# Main_Board.net
KiCad netlist of a schematic drawn in Altium Designer
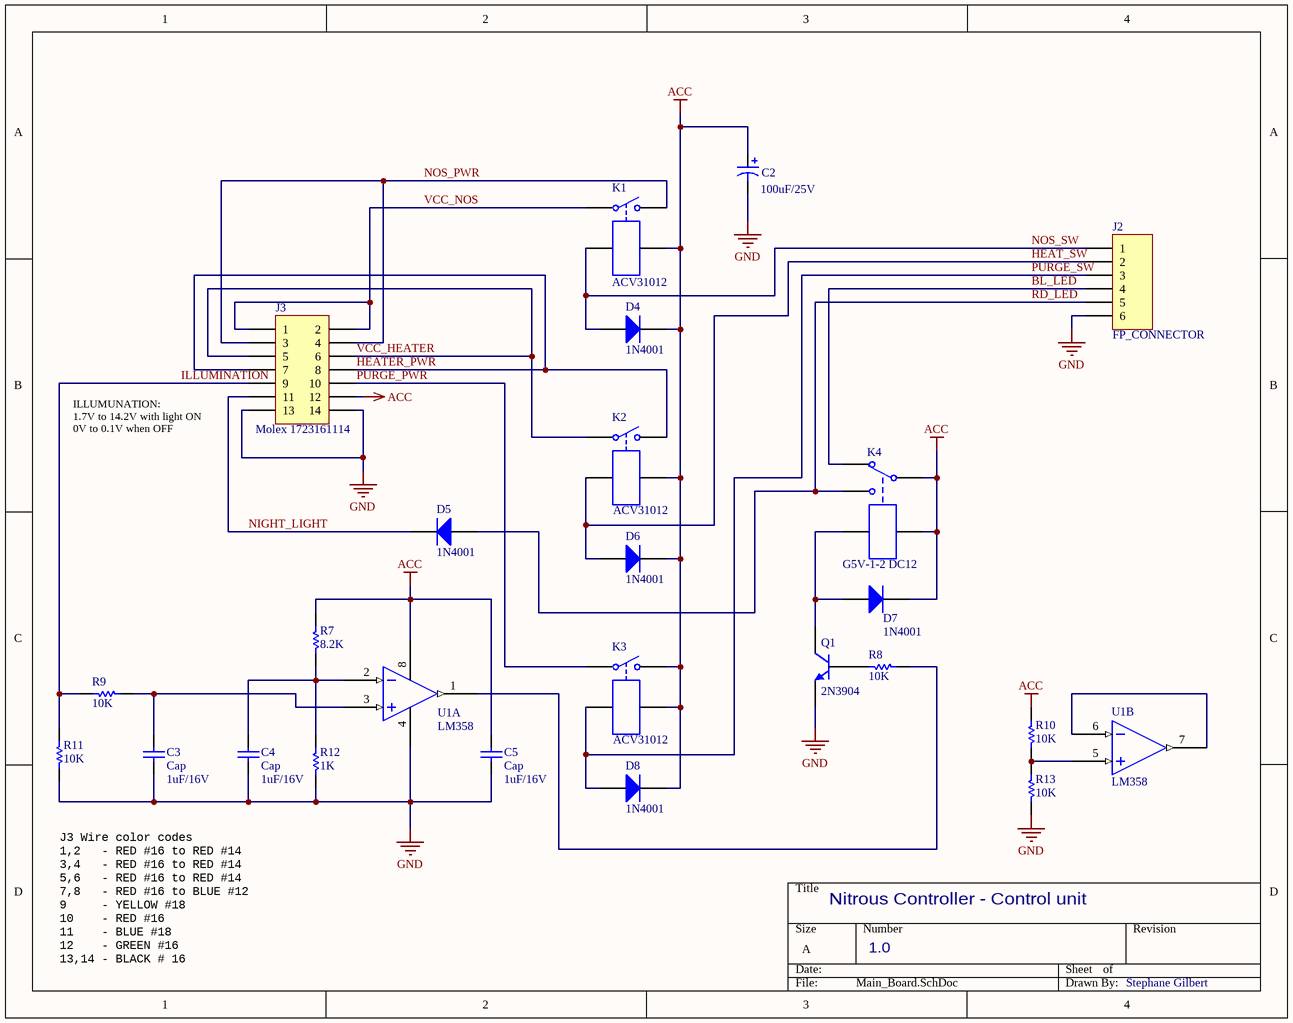
[diagram p0: Main_Board.SchDoc]

(export (version "E")
  (design (tool "Eeschema 10.0.6"))
  (components
    (comp (ref "C2")
      (value "100uF/25V")
      (footprint "RB_3.5MM")
      (description "UBW1E101MPD1TD")
      (fields (field (name "Comment") "Cap Pol1") (field (name "PUBLISHER") "Altium Limited"))
      (libsource (lib "Miscellaneous Devices") (part "Cap Pol1"))
    )
    (comp (ref "C3")
      (value "Cap")
      (footprint "RAD-0.2")
      (description "FA26X8R1E105KNU06")
      (fields (field (name "ALTIUM_VALUE") "1uF/16V") (field (name "PUBLISHER") "Altium Limited"))
      (libsource (lib "Miscellaneous Devices") (part "Cap"))
    )
    (comp (ref "C4")
      (value "Cap")
      (footprint "RAD-0.2")
      (description "FA26X8R1E105KNU06")
      (fields (field (name "ALTIUM_VALUE") "1uF/16V") (field (name "PUBLISHER") "Altium Limited"))
      (libsource (lib "Miscellaneous Devices") (part "Cap"))
    )
    (comp (ref "C5")
      (value "Cap")
      (footprint "RAD-0.2")
      (description "FA26X8R1E105KNU06")
      (fields (field (name "ALTIUM_VALUE") "1uF/16V") (field (name "PUBLISHER") "Altium Limited"))
      (libsource (lib "Miscellaneous Devices") (part "Cap"))
    )
    (comp (ref "D4")
      (value "1N4001")
      (footprint "DO-41")
      (description "1 Amp General Purpose Rectifier")
      (fields (field (name "PUBLISHER") "Altium Limited"))
      (libsource (lib "Miscellaneous Devices") (part "Diode 1N4001"))
    )
    (comp (ref "D5")
      (value "1N4001")
      (footprint "DO-41")
      (description "1 Amp General Purpose Rectifier")
      (fields (field (name "PUBLISHER") "Altium Limited"))
      (libsource (lib "Miscellaneous Devices") (part "Diode 1N4001"))
    )
    (comp (ref "D6")
      (value "1N4001")
      (footprint "DO-41")
      (description "1 Amp General Purpose Rectifier")
      (fields (field (name "PUBLISHER") "Altium Limited"))
      (libsource (lib "Miscellaneous Devices") (part "Diode 1N4001"))
    )
    (comp (ref "D7")
      (value "1N4001")
      (footprint "DO-41")
      (description "1 Amp General Purpose Rectifier")
      (fields (field (name "PUBLISHER") "Altium Limited"))
      (libsource (lib "Miscellaneous Devices") (part "Diode 1N4001"))
    )
    (comp (ref "D8")
      (value "1N4001")
      (footprint "DO-41")
      (description "1 Amp General Purpose Rectifier")
      (fields (field (name "PUBLISHER") "Altium Limited"))
      (libsource (lib "Miscellaneous Devices") (part "Diode 1N4001"))
    )
    (comp (ref "J2")
      (value "FP_CONNECTOR")
      (footprint "MOLEX_5329_6POS_RA")
      (description "Header, 6-Pin")
      (fields (field (name "PUBLISHER") "Altium Limited"))
      (libsource (lib "Miscellaneous Connectors") (part "Header 6"))
    )
    (comp (ref "J3")
      (value "Molex 1723161114")
      (footprint "MOLEX_ULTRA_FIT_14_POS_RA")
      (description "Header, 7-Pin, Dual row")
      (fields (field (name "PUBLISHER") "Altium Limited"))
      (libsource (lib "Miscellaneous Connectors") (part "Header 7X2"))
    )
    (comp (ref "K1")
      (value "ACV31012")
      (footprint "RL_MICRO_ISO_ACV")
      (description "Single-Pole Single-Throw Relay")
      (fields (field (name "PUBLISHER") "Altium Limited"))
      (libsource (lib "Miscellaneous Devices") (part "Relay-SPST"))
    )
    (comp (ref "K2")
      (value "ACV31012")
      (footprint "RL_MICRO_ISO_ACV")
      (description "Single-Pole Single-Throw Relay")
      (fields (field (name "PUBLISHER") "Altium Limited"))
      (libsource (lib "Miscellaneous Devices") (part "Relay-SPST"))
    )
    (comp (ref "K3")
      (value "ACV31012")
      (footprint "RL_MICRO_ISO_ACV")
      (description "Single-Pole Single-Throw Relay")
      (fields (field (name "PUBLISHER") "Altium Limited"))
      (libsource (lib "Miscellaneous Devices") (part "Relay-SPST"))
    )
    (comp (ref "K4")
      (value "G5V-1-2 DC12")
      (footprint "RL_G5V-1")
      (description "Single-Pole Dual-Throw Relay")
      (fields (field (name "PUBLISHER") "Altium Limited"))
      (libsource (lib "Miscellaneous Devices") (part "Relay-SPDT"))
    )
    (comp (ref "Q1")
      (value "2N3904")
      (footprint "TO-92")
      (description "NPN Bipolar Transistor")
      (fields (field (name "PUBLISHER") "Altium Limited"))
      (libsource (lib "Miscellaneous Devices") (part "NPN"))
    )
    (comp (ref "R7")
      (value "8.2K")
      (footprint "AXIAL-0.4")
      (description "Resistor")
      (fields (field (name "Comment") "Res1") (field (name "PUBLISHER") "Altium Limited"))
      (libsource (lib "Miscellaneous Devices") (part "Res1"))
    )
    (comp (ref "R8")
      (value "10K")
      (footprint "AXIAL-0.4")
      (description "Resistor")
      (fields (field (name "Comment") "Res1") (field (name "PUBLISHER") "Altium Limited"))
      (libsource (lib "Miscellaneous Devices") (part "Res1"))
    )
    (comp (ref "R9")
      (value "10K")
      (footprint "AXIAL-0.4")
      (description "Resistor")
      (fields (field (name "Comment") "Res1") (field (name "PUBLISHER") "Altium Limited"))
      (libsource (lib "Miscellaneous Devices") (part "Res1"))
    )
    (comp (ref "R10")
      (value "10K")
      (footprint "AXIAL-0.4")
      (description "Resistor")
      (fields (field (name "Comment") "Res1") (field (name "PUBLISHER") "Altium Limited"))
      (libsource (lib "Miscellaneous Devices") (part "Res1"))
    )
    (comp (ref "R11")
      (value "10K")
      (footprint "AXIAL-0.4")
      (description "Resistor")
      (fields (field (name "Comment") "Res1") (field (name "PUBLISHER") "Altium Limited"))
      (libsource (lib "Miscellaneous Devices") (part "Res1"))
    )
    (comp (ref "R12")
      (value "1K")
      (footprint "AXIAL-0.4")
      (description "Resistor")
      (fields (field (name "Comment") "Res1") (field (name "PUBLISHER") "Altium Limited"))
      (libsource (lib "Miscellaneous Devices") (part "Res1"))
    )
    (comp (ref "R13")
      (value "10K")
      (footprint "AXIAL-0.4")
      (description "Resistor")
      (fields (field (name "Comment") "Res1") (field (name "PUBLISHER") "Altium Limited"))
      (libsource (lib "Miscellaneous Devices") (part "Res1"))
    )
    (comp (ref "U1")
      (value "LM358")
      (footprint "Miscellaneous Devices:DIP-8")
      (libsource (lib "Nitrous") (part "LM358"))
    )
  )
  (nets
    (net (code "1") (name "/BL_LED") (class "Default")
      (node (ref "J2") (pin "4") (pinfunction "4_4") (pintype "passive"))
      (node (ref "K4") (pin "2") (pinfunction "2_2") (pintype "passive"))
    )
    (net (code "2") (name "/HEATER_PWR") (class "Default")
      (node (ref "J3") (pin "7") (pinfunction "7_7") (pintype "passive"))
      (node (ref "J3") (pin "8") (pinfunction "8_8") (pintype "passive"))
      (node (ref "K2") (pin "2") (pinfunction "2_2") (pintype "passive"))
    )
    (net (code "3") (name "/HEAT_SW") (class "Default")
      (node (ref "D6") (pin "1") (pinfunction "A_1") (pintype "passive"))
      (node (ref "J2") (pin "2") (pinfunction "2_2") (pintype "passive"))
      (node (ref "K2") (pin "3") (pinfunction "3_3") (pintype "passive"))
    )
    (net (code "4") (name "/ILLUMINATION") (class "Default")
      (node (ref "J3") (pin "9") (pinfunction "9_9") (pintype "passive"))
      (node (ref "R11") (pin "2") (pinfunction "2_2") (pintype "passive"))
      (node (ref "R9") (pin "2") (pinfunction "2_2") (pintype "passive"))
    )
    (net (code "5") (name "/NIGHT_LIGHT") (class "Default")
      (node (ref "D5") (pin "2") (pinfunction "K_2") (pintype "passive"))
      (node (ref "J3") (pin "11") (pinfunction "11_11") (pintype "passive"))
    )
    (net (code "6") (name "/NOS_PWR") (class "Default")
      (node (ref "J3") (pin "3") (pinfunction "3_3") (pintype "passive"))
      (node (ref "J3") (pin "4") (pinfunction "4_4") (pintype "passive"))
      (node (ref "K1") (pin "2") (pinfunction "2_2") (pintype "passive"))
    )
    (net (code "7") (name "/NOS_SW") (class "Default")
      (node (ref "D4") (pin "1") (pinfunction "A_1") (pintype "passive"))
      (node (ref "J2") (pin "1") (pinfunction "1_1") (pintype "passive"))
      (node (ref "K1") (pin "3") (pinfunction "3_3") (pintype "passive"))
    )
    (net (code "8") (name "/PURGE_PWR") (class "Default")
      (node (ref "J3") (pin "10") (pinfunction "10_10") (pintype "passive"))
      (node (ref "K3") (pin "1") (pinfunction "1_1") (pintype "passive"))
    )
    (net (code "9") (name "/PURGE_SW") (class "Default")
      (node (ref "D8") (pin "1") (pinfunction "A_1") (pintype "passive"))
      (node (ref "J2") (pin "3") (pinfunction "3_3") (pintype "passive"))
      (node (ref "K3") (pin "3") (pinfunction "3_3") (pintype "passive"))
    )
    (net (code "10") (name "/RD_LED") (class "Default")
      (node (ref "D5") (pin "1") (pinfunction "A_1") (pintype "passive"))
      (node (ref "J2") (pin "5") (pinfunction "5_5") (pintype "passive"))
      (node (ref "K4") (pin "3") (pinfunction "3_3") (pintype "passive"))
    )
    (net (code "11") (name "/VCC_HEATER") (class "Default")
      (node (ref "J3") (pin "5") (pinfunction "5_5") (pintype "passive"))
      (node (ref "J3") (pin "6") (pinfunction "6_6") (pintype "passive"))
      (node (ref "K2") (pin "1") (pinfunction "1_1") (pintype "passive"))
    )
    (net (code "12") (name "/VCC_NOS") (class "Default")
      (node (ref "J3") (pin "1") (pinfunction "1_1") (pintype "passive"))
      (node (ref "J3") (pin "2") (pinfunction "2_2") (pintype "passive"))
      (node (ref "K1") (pin "1") (pinfunction "1_1") (pintype "passive"))
    )
    (net (code "13") (name "ACC") (class "Default")
      (node (ref "C2") (pin "1") (pinfunction "1_1") (pintype "passive"))
      (node (ref "C5") (pin "2") (pinfunction "2_2") (pintype "passive"))
      (node (ref "D4") (pin "2") (pinfunction "K_2") (pintype "passive"))
      (node (ref "D6") (pin "2") (pinfunction "K_2") (pintype "passive"))
      (node (ref "D7") (pin "2") (pinfunction "K_2") (pintype "passive"))
      (node (ref "D8") (pin "2") (pinfunction "K_2") (pintype "passive"))
      (node (ref "J3") (pin "12") (pinfunction "12_12") (pintype "passive"))
      (node (ref "K1") (pin "4") (pinfunction "4_4") (pintype "passive"))
      (node (ref "K2") (pin "4") (pinfunction "4_4") (pintype "passive"))
      (node (ref "K3") (pin "2") (pinfunction "2_2") (pintype "passive"))
      (node (ref "K3") (pin "4") (pinfunction "4_4") (pintype "passive"))
      (node (ref "K4") (pin "1") (pinfunction "1_1") (pintype "passive"))
      (node (ref "K4") (pin "4") (pinfunction "4_4") (pintype "passive"))
      (node (ref "R10") (pin "1") (pinfunction "1_1") (pintype "passive"))
      (node (ref "R7") (pin "1") (pinfunction "1_1") (pintype "passive"))
      (node (ref "U1") (pin "8") (pinfunction "8_8") (pintype "power_in"))
    )
    (net (code "14") (name "GND") (class "Default")
      (node (ref "C2") (pin "2") (pinfunction "2_2") (pintype "passive"))
      (node (ref "C3") (pin "1") (pinfunction "1_1") (pintype "passive"))
      (node (ref "C4") (pin "1") (pinfunction "1_1") (pintype "passive"))
      (node (ref "C5") (pin "1") (pinfunction "1_1") (pintype "passive"))
      (node (ref "J2") (pin "6") (pinfunction "6_6") (pintype "passive"))
      (node (ref "J3") (pin "13") (pinfunction "13_13") (pintype "passive"))
      (node (ref "J3") (pin "14") (pinfunction "14_14") (pintype "passive"))
      (node (ref "Q1") (pin "3") (pinfunction "E_3") (pintype "passive"))
      (node (ref "R11") (pin "1") (pinfunction "1_1") (pintype "passive"))
      (node (ref "R12") (pin "2") (pinfunction "2_2") (pintype "passive"))
      (node (ref "R13") (pin "1") (pinfunction "1_1") (pintype "passive"))
      (node (ref "U1") (pin "4") (pinfunction "4_4") (pintype "power_in"))
    )
    (net (code "15") (name "Net-(C3-Pad2)") (class "Default")
      (node (ref "C3") (pin "2") (pinfunction "2_2") (pintype "passive"))
      (node (ref "R9") (pin "1") (pinfunction "1_1") (pintype "passive"))
      (node (ref "U1") (pin "3") (pinfunction "3_3") (pintype "input"))
    )
    (net (code "16") (name "Net-(C4-Pad2)") (class "Default")
      (node (ref "C4") (pin "2") (pinfunction "2_2") (pintype "passive"))
      (node (ref "R12") (pin "1") (pinfunction "1_1") (pintype "passive"))
      (node (ref "R7") (pin "2") (pinfunction "2_2") (pintype "passive"))
      (node (ref "U1") (pin "2") (pinfunction "2_2") (pintype "input"))
    )
    (net (code "17") (name "Net-(D7-A)") (class "Default")
      (node (ref "D7") (pin "1") (pinfunction "A_1") (pintype "passive"))
      (node (ref "K4") (pin "5") (pinfunction "5_5") (pintype "passive"))
      (node (ref "Q1") (pin "1") (pinfunction "C_1") (pintype "passive"))
    )
    (net (code "18") (name "Net-(Q1-B)") (class "Default")
      (node (ref "Q1") (pin "2") (pinfunction "B_2") (pintype "passive"))
      (node (ref "R8") (pin "2") (pinfunction "2_2") (pintype "passive"))
    )
    (net (code "19") (name "Net-(R8-Pad1)") (class "Default")
      (node (ref "R8") (pin "1") (pinfunction "1_1") (pintype "passive"))
      (node (ref "U1") (pin "1") (pinfunction "1_1") (pintype "output"))
    )
    (net (code "20") (name "Net-(R10-Pad2)") (class "Default")
      (node (ref "R10") (pin "2") (pinfunction "2_2") (pintype "passive"))
      (node (ref "R13") (pin "2") (pinfunction "2_2") (pintype "passive"))
      (node (ref "U1") (pin "5") (pinfunction "5_5") (pintype "input"))
    )
    (net (code "21") (name "Net-(U1-Pad6)") (class "Default")
      (node (ref "U1") (pin "6") (pinfunction "6_6") (pintype "input"))
      (node (ref "U1") (pin "7") (pinfunction "7_7") (pintype "output"))
    )
  )
)
